# nrf52840-contact-v03.net
KiCad netlist of a schematic drawn in EAGLE
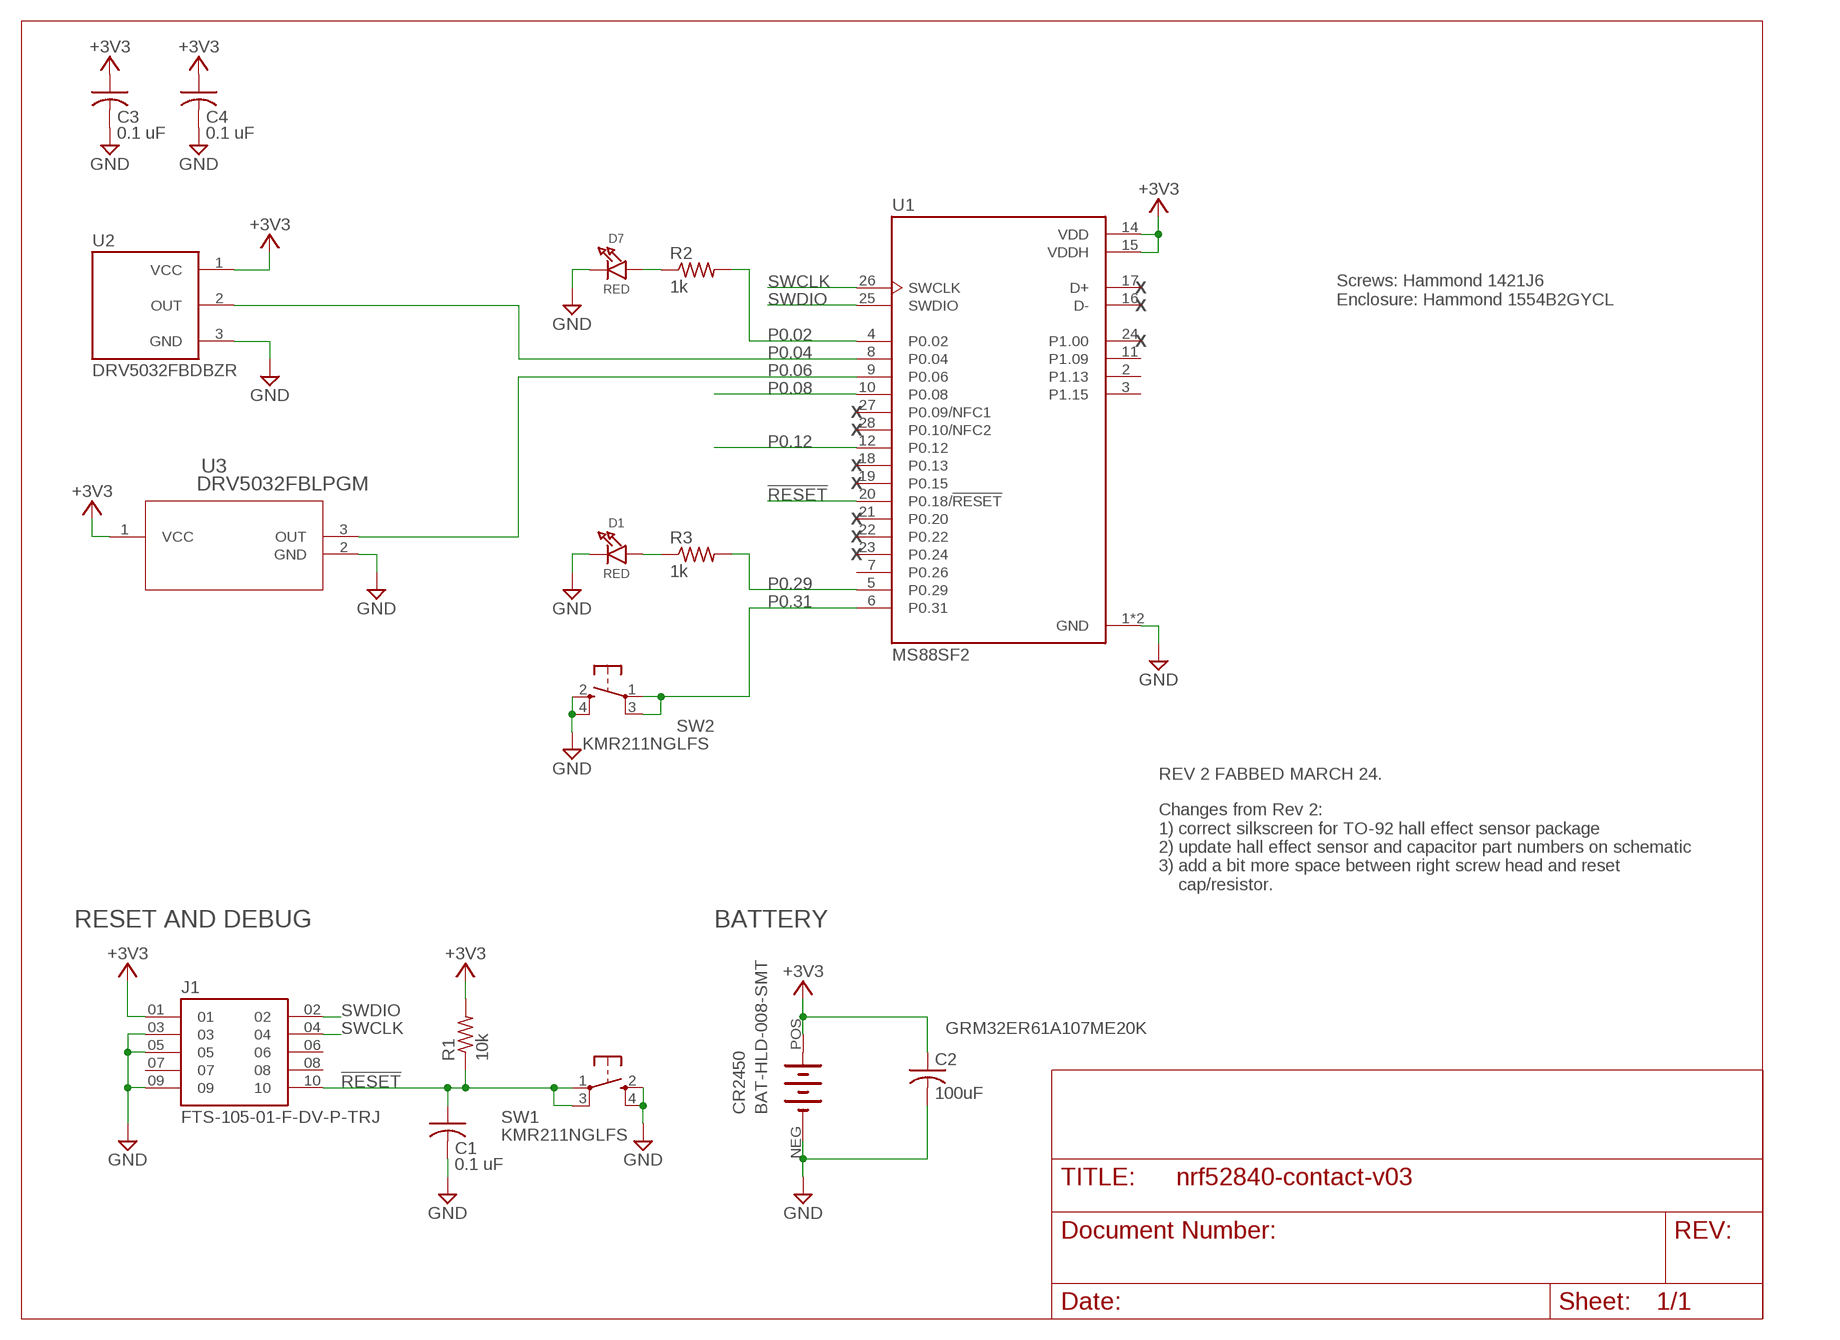
[diagram p0: schematic, sheet 1]

(export (version "E")
  (design (tool "Eeschema 10.0.6"))
  (components
    (comp (ref "C1")
      (value "0.1 uF")
      (footprint "eagle-import:C0603K")
      (libsource (lib "eagle-import") (part "C-USC0603K"))
    )
    (comp (ref "C2")
      (value "100uF")
      (footprint "eagle-import:C1210K")
      (libsource (lib "eagle-import") (part "C-USC1210K"))
    )
    (comp (ref "C3")
      (value "0.1 uF")
      (footprint "eagle-import:C0603K")
      (libsource (lib "eagle-import") (part "C-USC0603K"))
    )
    (comp (ref "C4")
      (value "0.1 uF")
      (footprint "eagle-import:C0603K")
      (libsource (lib "eagle-import") (part "C-USC0603K"))
    )
    (comp (ref "CR2450")
      (value "BAT-HLD-008-SMT")
      (footprint "eagle-import:BAT-HLD-008-SMT")
      (libsource (lib "eagle-import") (part "BAT-HLD-008-SMT"))
    )
    (comp (ref "D1")
      (value "RED")
      (footprint "eagle-import:CHIPLED_0805_NOOUTLINE")
      (libsource (lib "eagle-import") (part "LED0805_NOOUTLINE"))
    )
    (comp (ref "D7")
      (value "RED")
      (footprint "eagle-import:CHIPLED_0805_NOOUTLINE")
      (libsource (lib "eagle-import") (part "LED0805_NOOUTLINE"))
    )
    (comp (ref "J1")
      (value "FTS-105-01-F-DV-P-TRJ")
      (footprint "eagle-import:SAMTEC_FTS-105-01-F-DV-P-TR")
      (fields (field (name "MF") "Samtec") (field (name "MP") "FTS-105-01-F-DV-P-TR"))
      (libsource (lib "eagle-import") (part "FTS-105-01-F-DV-P-TRJ"))
    )
    (comp (ref "R1")
      (value "10k")
      (footprint "eagle-import:R0603")
      (libsource (lib "eagle-import") (part "R-US_R0603"))
    )
    (comp (ref "R2")
      (value "1k")
      (footprint "eagle-import:R0603")
      (libsource (lib "eagle-import") (part "R-US_R0603"))
    )
    (comp (ref "R3")
      (value "1k")
      (footprint "eagle-import:R0603")
      (libsource (lib "eagle-import") (part "R-US_R0603"))
    )
    (comp (ref "SW1")
      (value "KMR211NGLFS")
      (footprint "eagle-import:KMR2")
      (libsource (lib "eagle-import") (part "SPST_TACT-KMR2"))
    )
    (comp (ref "SW2")
      (value "KMR211NGLFS")
      (footprint "eagle-import:KMR2")
      (libsource (lib "eagle-import") (part "SPST_TACT-KMR2"))
    )
    (comp (ref "U1")
      (value "MS88SF2")
      (footprint "eagle-import:XCVR_MS88SF2")
      (fields (field (name "MF") "Minew"))
      (libsource (lib "eagle-import") (part "MS88SF2"))
    )
    (comp (ref "U2")
      (value "DRV5032FBDBZR")
      (footprint "eagle-import:SOT95P237X112-3N")
      (fields (field (name "MANUFACTURER") "Texas Instruments"))
      (libsource (lib "eagle-import") (part "DRV5032FBDBZR"))
    )
    (comp (ref "U3")
      (value "DRV5032FBLPGM")
      (footprint "eagle-import:TO-92-3_DRV5032A_4X3P15_TEX")
      (fields
        (field (name "MANUFACTURER_PART_NUMBER") "DRV5032AJLPG")
        (field (name "COPYRIGHT") "Copyright (C) 2024 Ultra Librarian. All rights reserved.")
      )
      (libsource (lib "eagle-import") (part "DRV5032AJLPG"))
    )
  )
  (nets
    (net (code "1") (name "+3V3") (class "Default")
      (node (ref "C2") (pin "1") (pinfunction "1_1") (pintype "passive"))
      (node (ref "C3") (pin "1") (pinfunction "1_1") (pintype "passive"))
      (node (ref "C4") (pin "1") (pinfunction "1_1") (pintype "passive"))
      (node (ref "CR2450") (pin "POS") (pinfunction "+_POS") (pintype "passive"))
      (node (ref "J1") (pin "01") (pinfunction "01_01") (pintype "passive"))
      (node (ref "R1") (pin "2") (pinfunction "2_2") (pintype "passive"))
      (node (ref "U1") (pin "14") (pinfunction "VDD_14") (pintype "power_in"))
      (node (ref "U1") (pin "15") (pinfunction "VDDH_15") (pintype "power_in"))
      (node (ref "U2") (pin "1") (pinfunction "VCC_1") (pintype "power_in"))
      (node (ref "U3") (pin "1") (pinfunction "VCC_1") (pintype "power_in"))
    )
    (net (code "2") (name "/P0.02") (class "Default")
      (node (ref "R2") (pin "2") (pinfunction "2_2") (pintype "passive"))
      (node (ref "U1") (pin "4") (pinfunction "P0.02_4") (pintype "bidirectional"))
    )
    (net (code "3") (name "/P0.04") (class "Default")
      (node (ref "U1") (pin "8") (pinfunction "P0.04_8") (pintype "bidirectional"))
      (node (ref "U2") (pin "2") (pinfunction "OUT_2") (pintype "output"))
    )
    (net (code "4") (name "/P0.06") (class "Default")
      (node (ref "U1") (pin "9") (pinfunction "P0.06_9") (pintype "bidirectional"))
      (node (ref "U3") (pin "3") (pinfunction "OUT_3") (pintype "output"))
    )
    (net (code "5") (name "/P0.08") (class "Default")
      (node (ref "U1") (pin "10") (pinfunction "P0.08_10") (pintype "bidirectional"))
    )
    (net (code "6") (name "/P0.12") (class "Default")
      (node (ref "U1") (pin "12") (pinfunction "P0.12_12") (pintype "bidirectional"))
    )
    (net (code "7") (name "/P0.29") (class "Default")
      (node (ref "R3") (pin "2") (pinfunction "2_2") (pintype "passive"))
      (node (ref "U1") (pin "5") (pinfunction "P0.29_5") (pintype "bidirectional"))
    )
    (net (code "8") (name "/P0.31") (class "Default")
      (node (ref "SW2") (pin "1") (pinfunction "P_1") (pintype "passive"))
      (node (ref "SW2") (pin "3") (pinfunction "P1_3") (pintype "passive"))
      (node (ref "U1") (pin "6") (pinfunction "P0.31_6") (pintype "bidirectional"))
    )
    (net (code "9") (name "/SWCLK") (class "Default")
      (node (ref "J1") (pin "04") (pinfunction "04_04") (pintype "passive"))
      (node (ref "U1") (pin "26") (pinfunction "SWCLK_26") (pintype "input"))
    )
    (net (code "10") (name "/SWDIO") (class "Default")
      (node (ref "J1") (pin "02") (pinfunction "02_02") (pintype "passive"))
      (node (ref "U1") (pin "25") (pinfunction "SWDIO_25") (pintype "bidirectional"))
    )
    (net (code "11") (name "/~{RESET}") (class "Default")
      (node (ref "C1") (pin "1") (pinfunction "1_1") (pintype "passive"))
      (node (ref "J1") (pin "10") (pinfunction "10_10") (pintype "passive"))
      (node (ref "R1") (pin "1") (pinfunction "1_1") (pintype "passive"))
      (node (ref "SW1") (pin "1") (pinfunction "P_1") (pintype "passive"))
      (node (ref "SW1") (pin "3") (pinfunction "P1_3") (pintype "passive"))
      (node (ref "U1") (pin "20") (pinfunction "P0.18/~{RESET}_20") (pintype "bidirectional"))
    )
    (net (code "12") (name "GND") (class "Default")
      (node (ref "C1") (pin "2") (pinfunction "2_2") (pintype "passive"))
      (node (ref "C2") (pin "2") (pinfunction "2_2") (pintype "passive"))
      (node (ref "C3") (pin "2") (pinfunction "2_2") (pintype "passive"))
      (node (ref "C4") (pin "2") (pinfunction "2_2") (pintype "passive"))
      (node (ref "CR2450") (pin "NEG") (pinfunction "-_NEG") (pintype "passive"))
      (node (ref "D1") (pin "C") (pinfunction "C_C") (pintype "passive"))
      (node (ref "D7") (pin "C") (pinfunction "C_C") (pintype "passive"))
      (node (ref "J1") (pin "03") (pinfunction "03_03") (pintype "passive"))
      (node (ref "J1") (pin "05") (pinfunction "05_05") (pintype "passive"))
      (node (ref "J1") (pin "09") (pinfunction "09_09") (pintype "passive"))
      (node (ref "SW1") (pin "2") (pinfunction "S_2") (pintype "passive"))
      (node (ref "SW1") (pin "4") (pinfunction "S1_4") (pintype "passive"))
      (node (ref "SW2") (pin "2") (pinfunction "S_2") (pintype "passive"))
      (node (ref "SW2") (pin "4") (pinfunction "S1_4") (pintype "passive"))
      (node (ref "U1") (pin "1") (pinfunction "GND_1") (pintype "power_in"))
      (node (ref "U1") (pin "13") (pinfunction "GND_13") (pintype "power_in"))
      (node (ref "U2") (pin "3") (pinfunction "GND_3") (pintype "power_in"))
      (node (ref "U3") (pin "2") (pinfunction "GND_2") (pintype "passive"))
    )
    (net (code "13") (name "Net-(D1-PadA)") (class "Default")
      (node (ref "D1") (pin "A") (pinfunction "A_A") (pintype "passive"))
      (node (ref "R3") (pin "1") (pinfunction "1_1") (pintype "passive"))
    )
    (net (code "14") (name "Net-(D7-PadA)") (class "Default")
      (node (ref "D7") (pin "A") (pinfunction "A_A") (pintype "passive"))
      (node (ref "R2") (pin "1") (pinfunction "1_1") (pintype "passive"))
    )
    (net (code "15") (name "unconnected-(J1-Pad06)") (class "Default")
      (node (ref "J1") (pin "06") (pinfunction "06_06") (pintype "passive"))
    )
    (net (code "16") (name "unconnected-(J1-Pad07)") (class "Default")
      (node (ref "J1") (pin "07") (pinfunction "07_07") (pintype "passive"))
    )
    (net (code "17") (name "unconnected-(J1-Pad08)") (class "Default")
      (node (ref "J1") (pin "08") (pinfunction "08_08") (pintype "passive"))
    )
    (net (code "18") (name "unconnected-(U1-D+-Pad17)") (class "Default")
      (node (ref "U1") (pin "17") (pinfunction "D+_17") (pintype "bidirectional"))
    )
    (net (code "19") (name "unconnected-(U1-D--Pad16)") (class "Default")
      (node (ref "U1") (pin "16") (pinfunction "D-_16") (pintype "bidirectional"))
    )
    (net (code "20") (name "unconnected-(U1-P0.09{slash}NFC1-Pad27)") (class "Default")
      (node (ref "U1") (pin "27") (pinfunction "P0.09/NFC1_27") (pintype "bidirectional"))
    )
    (net (code "21") (name "unconnected-(U1-P0.10{slash}NFC2-Pad28)") (class "Default")
      (node (ref "U1") (pin "28") (pinfunction "P0.10/NFC2_28") (pintype "bidirectional"))
    )
    (net (code "22") (name "unconnected-(U1-P0.13-Pad18)") (class "Default")
      (node (ref "U1") (pin "18") (pinfunction "P0.13_18") (pintype "bidirectional"))
    )
    (net (code "23") (name "unconnected-(U1-P0.15-Pad19)") (class "Default")
      (node (ref "U1") (pin "19") (pinfunction "P0.15_19") (pintype "bidirectional"))
    )
    (net (code "24") (name "unconnected-(U1-P0.20-Pad21)") (class "Default")
      (node (ref "U1") (pin "21") (pinfunction "P0.20_21") (pintype "bidirectional"))
    )
    (net (code "25") (name "unconnected-(U1-P0.22-Pad22)") (class "Default")
      (node (ref "U1") (pin "22") (pinfunction "P0.22_22") (pintype "bidirectional"))
    )
    (net (code "26") (name "unconnected-(U1-P0.24-Pad23)") (class "Default")
      (node (ref "U1") (pin "23") (pinfunction "P0.24_23") (pintype "bidirectional"))
    )
    (net (code "27") (name "unconnected-(U1-P0.26-Pad7)") (class "Default")
      (node (ref "U1") (pin "7") (pinfunction "P0.26_7") (pintype "bidirectional"))
    )
    (net (code "28") (name "unconnected-(U1-P1.00-Pad24)") (class "Default")
      (node (ref "U1") (pin "24") (pinfunction "P1.00_24") (pintype "bidirectional"))
    )
    (net (code "29") (name "unconnected-(U1-P1.09-Pad11)") (class "Default")
      (node (ref "U1") (pin "11") (pinfunction "P1.09_11") (pintype "bidirectional"))
    )
    (net (code "30") (name "unconnected-(U1-P1.13-Pad2)") (class "Default")
      (node (ref "U1") (pin "2") (pinfunction "P1.13_2") (pintype "bidirectional"))
    )
    (net (code "31") (name "unconnected-(U1-P1.15-Pad3)") (class "Default")
      (node (ref "U1") (pin "3") (pinfunction "P1.15_3") (pintype "bidirectional"))
    )
  )
)
